# page1.net
KiCad netlist of a schematic drawn in EAGLE
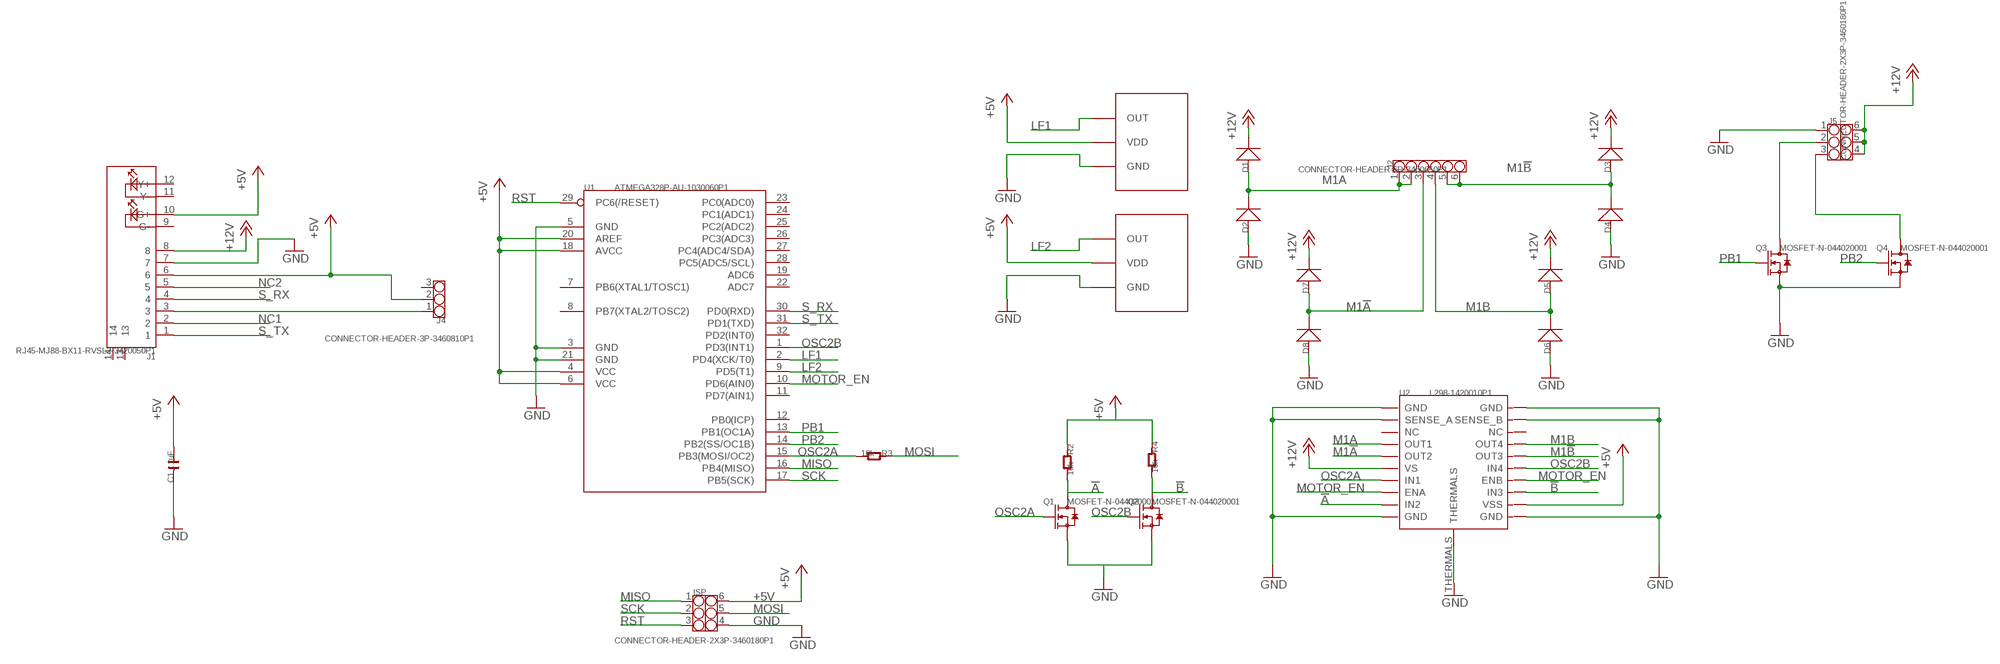
[diagram p0: schematic, sheet 1]

(export (version "E")
  (design (tool "Eeschema 10.0.6"))
  (components
    (comp (ref "C1")
      (value "1uF")
      (footprint "eagle-import:C0805")
      (libsource (lib "eagle-import") (part "C-0805"))
    )
    (comp (ref "D1")
      (value "D-SMA")
      (footprint "eagle-import:DO-214AC")
      (libsource (lib "eagle-import") (part "D-SMA"))
    )
    (comp (ref "D2")
      (value "D-SMA")
      (footprint "eagle-import:DO-214AC")
      (libsource (lib "eagle-import") (part "D-SMA"))
    )
    (comp (ref "D3")
      (value "D-SMA")
      (footprint "eagle-import:DO-214AC")
      (libsource (lib "eagle-import") (part "D-SMA"))
    )
    (comp (ref "D4")
      (value "D-SMA")
      (footprint "eagle-import:DO-214AC")
      (libsource (lib "eagle-import") (part "D-SMA"))
    )
    (comp (ref "D5")
      (value "D-SMA")
      (footprint "eagle-import:DO-214AC")
      (libsource (lib "eagle-import") (part "D-SMA"))
    )
    (comp (ref "D6")
      (value "D-SMA")
      (footprint "eagle-import:DO-214AC")
      (libsource (lib "eagle-import") (part "D-SMA"))
    )
    (comp (ref "D7")
      (value "D-SMA")
      (footprint "eagle-import:DO-214AC")
      (libsource (lib "eagle-import") (part "D-SMA"))
    )
    (comp (ref "D8")
      (value "D-SMA")
      (footprint "eagle-import:DO-214AC")
      (libsource (lib "eagle-import") (part "D-SMA"))
    )
    (comp (ref "ISP")
      (value "CONNECTOR-HEADER-2X3P-3460180P1")
      (footprint "eagle-import:2X3P-2.54-2.54-11.6-3.0-BLACK-MALE")
      (libsource (lib "eagle-import") (part "CONNECTOR-HEADER-2X3P-3460180P1"))
    )
    (comp (ref "J1")
      (value "RJ45-MJ88-BX11-RVSL2-3420050P1")
      (footprint "eagle-import:RJ45-MJ88-BX11-RVSL2")
      (libsource (lib "eagle-import") (part "RJ45-MJ88-BX11-RVSL2-3420050P1"))
    )
    (comp (ref "J2")
      (value "CONNECTOR-HEADER-6P-3460650P1")
      (footprint "eagle-import:1X6P-2.54-2.54-11.6-3.0-BLACK-MALE")
      (libsource (lib "eagle-import") (part "CONNECTOR-HEADER-6P-3460650P1"))
    )
    (comp (ref "J4")
      (value "CONNECTOR-HEADER-3P-3460810P1")
      (footprint "eagle-import:1X3P-2.54-2.54-11.6-3.0-BLACK-MALE")
      (libsource (lib "eagle-import") (part "CONNECTOR-HEADER-3P-3460810P1"))
    )
    (comp (ref "J5")
      (value "CONNECTOR-HEADER-2X3P-3460180P1")
      (footprint "eagle-import:2X3P-2.54-2.54-11.6-3.0-BLACK-MALE")
      (libsource (lib "eagle-import") (part "CONNECTOR-HEADER-2X3P-3460180P1"))
    )
    (comp (ref "Q1")
      (value "MOSFET-N-044020001")
      (footprint "eagle-import:SOT23")
      (libsource (lib "eagle-import") (part "MOSFET-N-044020001"))
    )
    (comp (ref "Q2")
      (value "MOSFET-N-044020001")
      (footprint "eagle-import:SOT23")
      (libsource (lib "eagle-import") (part "MOSFET-N-044020001"))
    )
    (comp (ref "Q3")
      (value "MOSFET-N-044020001")
      (footprint "eagle-import:SOT23")
      (libsource (lib "eagle-import") (part "MOSFET-N-044020001"))
    )
    (comp (ref "Q4")
      (value "MOSFET-N-044020001")
      (footprint "eagle-import:SOT23")
      (libsource (lib "eagle-import") (part "MOSFET-N-044020001"))
    )
    (comp (ref "R2")
      (value "10k")
      (footprint "eagle-import:R0603")
      (libsource (lib "eagle-import") (part "R-0603"))
    )
    (comp (ref "R3")
      (value "10k")
      (footprint "eagle-import:R0603")
      (libsource (lib "eagle-import") (part "R-0603"))
    )
    (comp (ref "R4")
      (value "10k")
      (footprint "eagle-import:R0603")
      (libsource (lib "eagle-import") (part "R-0603"))
    )
    (comp (ref "U$5")
      (value "TSL235")
      (footprint "eagle-import:TSL235R-2MM-S")
      (libsource (lib "eagle-import") (part "TSL235"))
    )
    (comp (ref "U$6")
      (value "TSL235")
      (footprint "eagle-import:TSL235R-2MM-S")
      (libsource (lib "eagle-import") (part "TSL235"))
    )
    (comp (ref "U1")
      (value "ATMEGA328P-AU-1030060P1")
      (footprint "eagle-import:TQFP32")
      (libsource (lib "eagle-import") (part "ATMEGA328P-AU-1030060P1"))
    )
    (comp (ref "U2")
      (value "L298-1420010P1")
      (footprint "eagle-import:POWERSO-20")
      (libsource (lib "eagle-import") (part "L298-1420010P1"))
    )
  )
  (nets
    (net (code "1") (name "+5V") (class "Default")
      (node (ref "C1") (pin "2") (pinfunction "2_2") (pintype "bidirectional"))
      (node (ref "ISP") (pin "6") (pinfunction "6_6") (pintype "bidirectional"))
      (node (ref "J1") (pin "10") (pinfunction "G+_10") (pintype "bidirectional"))
      (node (ref "J1") (pin "6") (pinfunction "6_6") (pintype "bidirectional"))
      (node (ref "J4") (pin "2") (pinfunction "2_2") (pintype "bidirectional"))
      (node (ref "R2") (pin "1") (pinfunction "1_1") (pintype "bidirectional"))
      (node (ref "R4") (pin "1") (pinfunction "1_1") (pintype "bidirectional"))
      (node (ref "U$5") (pin "P$2") (pinfunction "VDD_P$2") (pintype "bidirectional"))
      (node (ref "U$6") (pin "P$2") (pinfunction "VDD_P$2") (pintype "bidirectional"))
      (node (ref "U1") (pin "18") (pinfunction "AVCC_18") (pintype "bidirectional"))
      (node (ref "U1") (pin "20") (pinfunction "AREF_20") (pintype "bidirectional"))
      (node (ref "U1") (pin "4") (pinfunction "VCC_4") (pintype "bidirectional"))
      (node (ref "U1") (pin "6") (pinfunction "VCC_6") (pintype "bidirectional"))
      (node (ref "U2") (pin "12") (pinfunction "VSS_12") (pintype "bidirectional"))
    )
    (net (code "2") (name "+12V") (class "Default")
      (node (ref "D1") (pin "2") (pinfunction "-_2") (pintype "passive"))
      (node (ref "D3") (pin "2") (pinfunction "-_2") (pintype "passive"))
      (node (ref "D5") (pin "2") (pinfunction "-_2") (pintype "passive"))
      (node (ref "D7") (pin "2") (pinfunction "-_2") (pintype "passive"))
      (node (ref "J1") (pin "8") (pinfunction "8_8") (pintype "bidirectional"))
      (node (ref "J5") (pin "4") (pinfunction "4_4") (pintype "bidirectional"))
      (node (ref "J5") (pin "5") (pinfunction "5_5") (pintype "bidirectional"))
      (node (ref "J5") (pin "6") (pinfunction "6_6") (pintype "bidirectional"))
      (node (ref "U2") (pin "6") (pinfunction "VS_6") (pintype "bidirectional"))
    )
    (net (code "3") (name "/LF1") (class "Default")
      (node (ref "U$5") (pin "P$3") (pinfunction "OUT_P$3") (pintype "output"))
      (node (ref "U1") (pin "2") (pinfunction "PD4(XCK/T0)_2") (pintype "bidirectional"))
    )
    (net (code "4") (name "/LF2") (class "Default")
      (node (ref "U$6") (pin "P$3") (pinfunction "OUT_P$3") (pintype "output"))
      (node (ref "U1") (pin "9") (pinfunction "PD5(T1)_9") (pintype "bidirectional"))
    )
    (net (code "5") (name "/M1A") (class "Default")
      (node (ref "D1") (pin "1") (pinfunction "+_1") (pintype "passive"))
      (node (ref "D2") (pin "2") (pinfunction "-_2") (pintype "passive"))
      (node (ref "J2") (pin "1") (pinfunction "1_1") (pintype "bidirectional"))
      (node (ref "J2") (pin "2") (pinfunction "2_2") (pintype "bidirectional"))
      (node (ref "U2") (pin "4") (pinfunction "OUT1_4") (pintype "bidirectional"))
    )
    (net (code "6") (name "/M1B") (class "Default")
      (node (ref "D5") (pin "1") (pinfunction "+_1") (pintype "passive"))
      (node (ref "D6") (pin "2") (pinfunction "-_2") (pintype "passive"))
      (node (ref "J2") (pin "4") (pinfunction "4_4") (pintype "bidirectional"))
      (node (ref "U2") (pin "17") (pinfunction "OUT4_17") (pintype "bidirectional"))
    )
    (net (code "7") (name "/M1~{A}") (class "Default")
      (node (ref "D7") (pin "1") (pinfunction "+_1") (pintype "passive"))
      (node (ref "D8") (pin "2") (pinfunction "-_2") (pintype "passive"))
      (node (ref "J2") (pin "3") (pinfunction "3_3") (pintype "bidirectional"))
      (node (ref "U2") (pin "5") (pinfunction "OUT2_5") (pintype "bidirectional"))
    )
    (net (code "8") (name "/M1~{B}") (class "Default")
      (node (ref "D3") (pin "1") (pinfunction "+_1") (pintype "passive"))
      (node (ref "D4") (pin "2") (pinfunction "-_2") (pintype "passive"))
      (node (ref "J2") (pin "5") (pinfunction "5_5") (pintype "bidirectional"))
      (node (ref "J2") (pin "6") (pinfunction "6_6") (pintype "bidirectional"))
      (node (ref "U2") (pin "16") (pinfunction "OUT3_16") (pintype "bidirectional"))
    )
    (net (code "9") (name "/MISO") (class "Default")
      (node (ref "ISP") (pin "1") (pinfunction "1_1") (pintype "bidirectional"))
      (node (ref "U1") (pin "16") (pinfunction "PB4(MISO)_16") (pintype "bidirectional"))
    )
    (net (code "10") (name "/MOSI") (class "Default")
      (node (ref "ISP") (pin "5") (pinfunction "5_5") (pintype "bidirectional"))
      (node (ref "R3") (pin "1") (pinfunction "1_1") (pintype "bidirectional"))
    )
    (net (code "11") (name "/MOTOR_EN") (class "Default")
      (node (ref "U1") (pin "10") (pinfunction "PD6(AIN0)_10") (pintype "bidirectional"))
      (node (ref "U2") (pin "14") (pinfunction "ENB_14") (pintype "bidirectional"))
      (node (ref "U2") (pin "8") (pinfunction "ENA_8") (pintype "bidirectional"))
    )
    (net (code "12") (name "/NC1") (class "Default")
      (node (ref "J1") (pin "2") (pinfunction "2_2") (pintype "bidirectional"))
    )
    (net (code "13") (name "/NC2") (class "Default")
      (node (ref "J1") (pin "5") (pinfunction "5_5") (pintype "bidirectional"))
    )
    (net (code "14") (name "/OSC2A") (class "Default")
      (node (ref "Q1") (pin "1") (pinfunction "G_1") (pintype "passive"))
      (node (ref "R3") (pin "2") (pinfunction "2_2") (pintype "bidirectional"))
      (node (ref "U1") (pin "15") (pinfunction "PB3(MOSI/OC2)_15") (pintype "bidirectional"))
      (node (ref "U2") (pin "7") (pinfunction "IN1_7") (pintype "bidirectional"))
    )
    (net (code "15") (name "/OSC2B") (class "Default")
      (node (ref "Q2") (pin "1") (pinfunction "G_1") (pintype "passive"))
      (node (ref "U1") (pin "1") (pinfunction "PD3(INT1)_1") (pintype "bidirectional"))
      (node (ref "U2") (pin "15") (pinfunction "IN4_15") (pintype "bidirectional"))
    )
    (net (code "16") (name "/PB1") (class "Default")
      (node (ref "Q3") (pin "1") (pinfunction "G_1") (pintype "passive"))
      (node (ref "U1") (pin "13") (pinfunction "PB1(OC1A)_13") (pintype "bidirectional"))
    )
    (net (code "17") (name "/PB2") (class "Default")
      (node (ref "Q4") (pin "1") (pinfunction "G_1") (pintype "passive"))
      (node (ref "U1") (pin "14") (pinfunction "PB2(SS/OC1B)_14") (pintype "bidirectional"))
    )
    (net (code "18") (name "/RST") (class "Default")
      (node (ref "ISP") (pin "3") (pinfunction "3_3") (pintype "bidirectional"))
      (node (ref "U1") (pin "29") (pinfunction "PC6(/RESET)_29") (pintype "bidirectional"))
    )
    (net (code "19") (name "/SCK") (class "Default")
      (node (ref "ISP") (pin "2") (pinfunction "2_2") (pintype "bidirectional"))
      (node (ref "U1") (pin "17") (pinfunction "PB5(SCK)_17") (pintype "bidirectional"))
    )
    (net (code "20") (name "/S_RX") (class "Default")
      (node (ref "J1") (pin "4") (pinfunction "4_4") (pintype "bidirectional"))
      (node (ref "U1") (pin "30") (pinfunction "PD0(RXD)_30") (pintype "bidirectional"))
    )
    (net (code "21") (name "/S_TX") (class "Default")
      (node (ref "J1") (pin "1") (pinfunction "1_1") (pintype "bidirectional"))
      (node (ref "U1") (pin "31") (pinfunction "PD1(TXD)_31") (pintype "bidirectional"))
    )
    (net (code "22") (name "/~{A}") (class "Default")
      (node (ref "Q1") (pin "3") (pinfunction "D_3") (pintype "passive"))
      (node (ref "R2") (pin "2") (pinfunction "2_2") (pintype "bidirectional"))
      (node (ref "U2") (pin "9") (pinfunction "IN2_9") (pintype "bidirectional"))
    )
    (net (code "23") (name "/~{B}") (class "Default")
      (node (ref "Q2") (pin "3") (pinfunction "D_3") (pintype "passive"))
      (node (ref "R4") (pin "2") (pinfunction "2_2") (pintype "bidirectional"))
      (node (ref "U2") (pin "13") (pinfunction "IN3_13") (pintype "bidirectional"))
    )
    (net (code "24") (name "GND") (class "Default")
      (node (ref "C1") (pin "1") (pinfunction "1_1") (pintype "bidirectional"))
      (node (ref "D2") (pin "1") (pinfunction "+_1") (pintype "passive"))
      (node (ref "D4") (pin "1") (pinfunction "+_1") (pintype "passive"))
      (node (ref "D6") (pin "1") (pinfunction "+_1") (pintype "passive"))
      (node (ref "D8") (pin "1") (pinfunction "+_1") (pintype "passive"))
      (node (ref "ISP") (pin "4") (pinfunction "4_4") (pintype "bidirectional"))
      (node (ref "J1") (pin "7") (pinfunction "7_7") (pintype "bidirectional"))
      (node (ref "J5") (pin "1") (pinfunction "1_1") (pintype "bidirectional"))
      (node (ref "Q1") (pin "2") (pinfunction "S_2") (pintype "passive"))
      (node (ref "Q2") (pin "2") (pinfunction "S_2") (pintype "passive"))
      (node (ref "Q3") (pin "2") (pinfunction "S_2") (pintype "passive"))
      (node (ref "Q4") (pin "2") (pinfunction "S_2") (pintype "passive"))
      (node (ref "U$5") (pin "P$1") (pinfunction "GND_P$1") (pintype "bidirectional"))
      (node (ref "U$6") (pin "P$1") (pinfunction "GND_P$1") (pintype "bidirectional"))
      (node (ref "U1") (pin "21") (pinfunction "GND_21") (pintype "bidirectional"))
      (node (ref "U1") (pin "3") (pinfunction "GND_3") (pintype "bidirectional"))
      (node (ref "U1") (pin "5") (pinfunction "GND_5") (pintype "bidirectional"))
      (node (ref "U2") (pin "1") (pinfunction "GND_1") (pintype "bidirectional"))
      (node (ref "U2") (pin "10") (pinfunction "GND_10") (pintype "bidirectional"))
      (node (ref "U2") (pin "11") (pinfunction "GND_11") (pintype "bidirectional"))
      (node (ref "U2") (pin "19") (pinfunction "SENSE_B_19") (pintype "bidirectional"))
      (node (ref "U2") (pin "2") (pinfunction "SENSE_A_2") (pintype "bidirectional"))
      (node (ref "U2") (pin "20") (pinfunction "GND_20") (pintype "bidirectional"))
      (node (ref "U2") (pin "THERMALS") (pinfunction "THERMALS_THERMALS") (pintype "bidirectional"))
    )
    (net (code "25") (name "Net-(J1-Pad3)") (class "Default")
      (node (ref "J1") (pin "3") (pinfunction "3_3") (pintype "bidirectional"))
      (node (ref "J4") (pin "1") (pinfunction "1_1") (pintype "bidirectional"))
    )
    (net (code "26") (name "Net-(Q3-D)") (class "Default")
      (node (ref "J5") (pin "2") (pinfunction "2_2") (pintype "bidirectional"))
      (node (ref "Q3") (pin "3") (pinfunction "D_3") (pintype "passive"))
    )
    (net (code "27") (name "Net-(Q4-D)") (class "Default")
      (node (ref "J5") (pin "3") (pinfunction "3_3") (pintype "bidirectional"))
      (node (ref "Q4") (pin "3") (pinfunction "D_3") (pintype "passive"))
    )
    (net (code "28") (name "unconnected-(J1-G--Pad9)") (class "Default")
      (node (ref "J1") (pin "9") (pinfunction "G-_9") (pintype "bidirectional"))
    )
    (net (code "29") (name "unconnected-(J1-Pad13)") (class "Default")
      (node (ref "J1") (pin "13") (pinfunction "13_13") (pintype "bidirectional"))
    )
    (net (code "30") (name "unconnected-(J1-Pad14)") (class "Default")
      (node (ref "J1") (pin "14") (pinfunction "14_14") (pintype "bidirectional"))
    )
    (net (code "31") (name "unconnected-(J1-Y+-Pad12)") (class "Default")
      (node (ref "J1") (pin "12") (pinfunction "Y+_12") (pintype "bidirectional"))
    )
    (net (code "32") (name "unconnected-(J1-Y--Pad11)") (class "Default")
      (node (ref "J1") (pin "11") (pinfunction "Y-_11") (pintype "bidirectional"))
    )
    (net (code "33") (name "unconnected-(J4-Pad3)") (class "Default")
      (node (ref "J4") (pin "3") (pinfunction "3_3") (pintype "bidirectional"))
    )
    (net (code "34") (name "unconnected-(U1-ADC6-Pad19)") (class "Default")
      (node (ref "U1") (pin "19") (pinfunction "ADC6_19") (pintype "bidirectional"))
    )
    (net (code "35") (name "unconnected-(U1-ADC7-Pad22)") (class "Default")
      (node (ref "U1") (pin "22") (pinfunction "ADC7_22") (pintype "bidirectional"))
    )
    (net (code "36") (name "unconnected-(U1-PB0(ICP)-Pad12)") (class "Default")
      (node (ref "U1") (pin "12") (pinfunction "PB0(ICP)_12") (pintype "bidirectional"))
    )
    (net (code "37") (name "unconnected-(U1-PB6(XTAL1{slash}TOSC1)-Pad7)") (class "Default")
      (node (ref "U1") (pin "7") (pinfunction "PB6(XTAL1/TOSC1)_7") (pintype "bidirectional"))
    )
    (net (code "38") (name "unconnected-(U1-PB7(XTAL2{slash}TOSC2)-Pad8)") (class "Default")
      (node (ref "U1") (pin "8") (pinfunction "PB7(XTAL2/TOSC2)_8") (pintype "bidirectional"))
    )
    (net (code "39") (name "unconnected-(U1-PC0(ADC0)-Pad23)") (class "Default")
      (node (ref "U1") (pin "23") (pinfunction "PC0(ADC0)_23") (pintype "bidirectional"))
    )
    (net (code "40") (name "unconnected-(U1-PC1(ADC1)-Pad24)") (class "Default")
      (node (ref "U1") (pin "24") (pinfunction "PC1(ADC1)_24") (pintype "bidirectional"))
    )
    (net (code "41") (name "unconnected-(U1-PC2(ADC2)-Pad25)") (class "Default")
      (node (ref "U1") (pin "25") (pinfunction "PC2(ADC2)_25") (pintype "bidirectional"))
    )
    (net (code "42") (name "unconnected-(U1-PC3(ADC3)-Pad26)") (class "Default")
      (node (ref "U1") (pin "26") (pinfunction "PC3(ADC3)_26") (pintype "bidirectional"))
    )
    (net (code "43") (name "unconnected-(U1-PC4(ADC4{slash}SDA)-Pad27)") (class "Default")
      (node (ref "U1") (pin "27") (pinfunction "PC4(ADC4/SDA)_27") (pintype "bidirectional"))
    )
    (net (code "44") (name "unconnected-(U1-PC5(ADC5{slash}SCL)-Pad28)") (class "Default")
      (node (ref "U1") (pin "28") (pinfunction "PC5(ADC5/SCL)_28") (pintype "bidirectional"))
    )
    (net (code "45") (name "unconnected-(U1-PD2(INT0)-Pad32)") (class "Default")
      (node (ref "U1") (pin "32") (pinfunction "PD2(INT0)_32") (pintype "bidirectional"))
    )
    (net (code "46") (name "unconnected-(U1-PD7(AIN1)-Pad11)") (class "Default")
      (node (ref "U1") (pin "11") (pinfunction "PD7(AIN1)_11") (pintype "bidirectional"))
    )
    (net (code "47") (name "unconnected-(U2-NC-Pad3)") (class "Default")
      (node (ref "U2") (pin "3") (pinfunction "NC_3") (pintype "bidirectional"))
    )
    (net (code "48") (name "unconnected-(U2-NC-Pad18)") (class "Default")
      (node (ref "U2") (pin "18") (pinfunction "NC_18") (pintype "bidirectional"))
    )
  )
)
